# HWK_2_Schematic.net
KiCad netlist of a schematic drawn in EAGLE
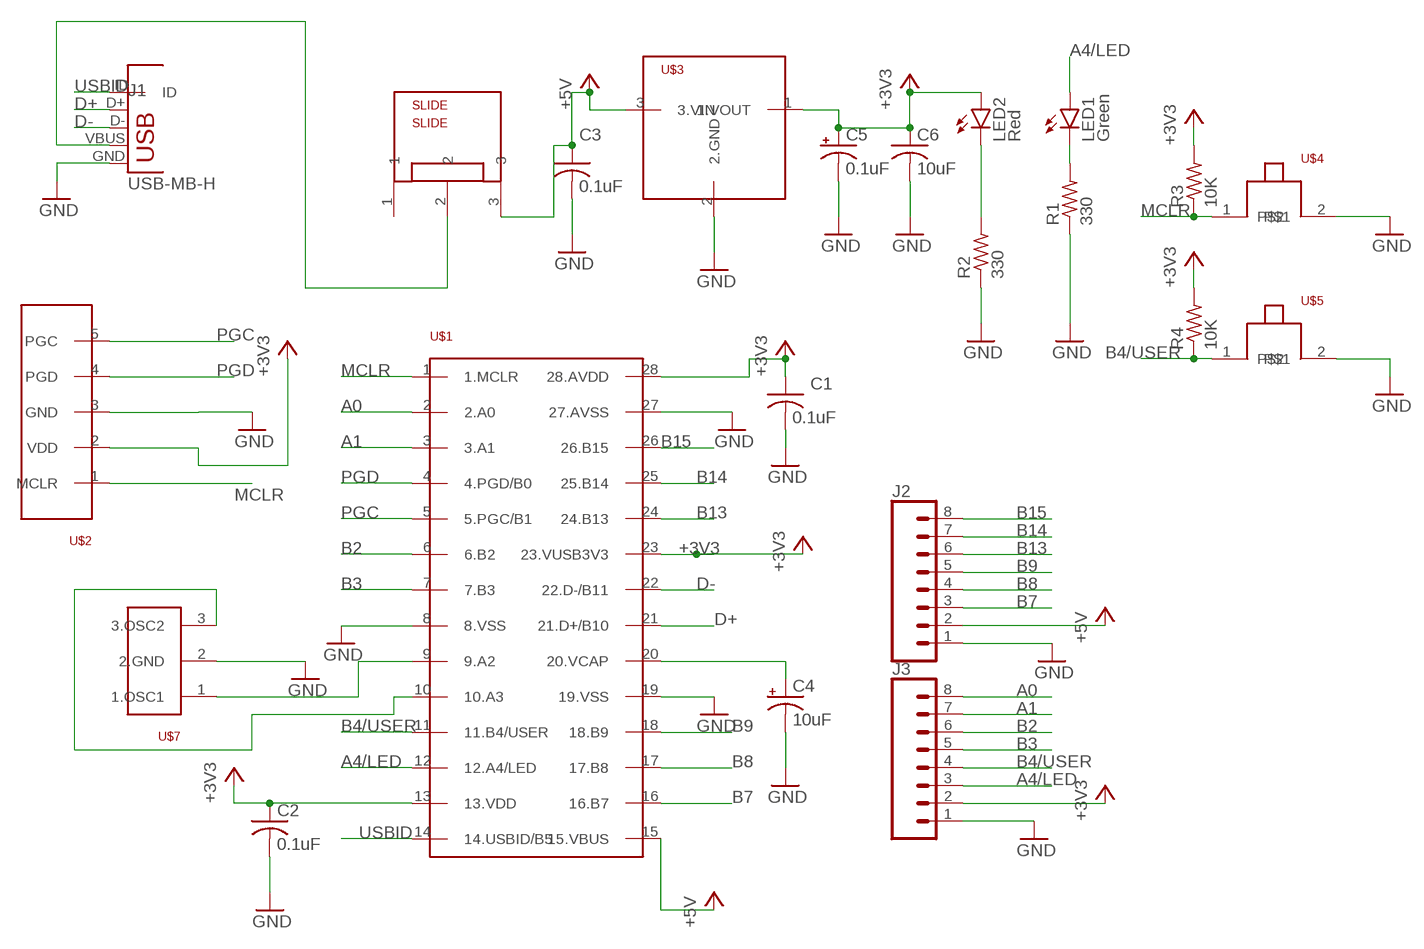
[diagram p0: schematic, sheet 1]

(export (version "E")
  (design (tool "Eeschema 10.0.6"))
  (components
    (comp (ref "C1")
      (value "0.1uF")
      (footprint "eagle-import:C025-025X050")
      (libsource (lib "eagle-import") (part "C-US025-025X050"))
    )
    (comp (ref "C2")
      (value "0.1uF")
      (footprint "eagle-import:C025-025X050")
      (libsource (lib "eagle-import") (part "C-US025-025X050"))
    )
    (comp (ref "C3")
      (value "0.1uF")
      (footprint "eagle-import:C025-025X050")
      (libsource (lib "eagle-import") (part "C-US025-025X050"))
    )
    (comp (ref "C4")
      (value "10uF")
      (footprint "eagle-import:B45181B")
      (libsource (lib "eagle-import") (part "CPOL-USB45181B"))
    )
    (comp (ref "C5")
      (value "0.1uF")
      (footprint "eagle-import:B45181B")
      (libsource (lib "eagle-import") (part "CPOL-USB45181B"))
    )
    (comp (ref "C6")
      (value "10uF")
      (footprint "eagle-import:C025-025X050")
      (libsource (lib "eagle-import") (part "C-US025-025X050"))
    )
    (comp (ref "J1")
      (value "USB-MB-H")
      (footprint "eagle-import:USB-MB-H")
      (libsource (lib "eagle-import") (part "USB-MB-H"))
    )
    (comp (ref "J2")
      (value "CONN_08NO_SILK_FEMALE_PTH")
      (footprint "eagle-import:1X08_NO_SILK")
      (libsource (lib "eagle-import") (part "CONN_08NO_SILK_FEMALE_PTH"))
    )
    (comp (ref "J3")
      (value "CONN_08NO_SILK_FEMALE_PTH")
      (footprint "eagle-import:1X08_NO_SILK")
      (libsource (lib "eagle-import") (part "CONN_08NO_SILK_FEMALE_PTH"))
    )
    (comp (ref "LED1")
      (value "Green")
      (footprint "eagle-import:LED3MM")
      (libsource (lib "eagle-import") (part "LED3MM"))
    )
    (comp (ref "LED2")
      (value "Red")
      (footprint "eagle-import:LED3MM")
      (libsource (lib "eagle-import") (part "LED3MM"))
    )
    (comp (ref "R1")
      (value "330")
      (footprint "eagle-import:0207_10")
      (libsource (lib "eagle-import") (part "R-US_0207/10"))
    )
    (comp (ref "R2")
      (value "330")
      (footprint "eagle-import:0207_10")
      (libsource (lib "eagle-import") (part "R-US_0207/10"))
    )
    (comp (ref "R3")
      (value "10K")
      (footprint "eagle-import:0207_10")
      (libsource (lib "eagle-import") (part "R-US_0207/10"))
    )
    (comp (ref "R4")
      (value "10K")
      (footprint "eagle-import:0207_10")
      (libsource (lib "eagle-import") (part "R-US_0207/10"))
    )
    (comp (ref "SLIDE")
      (value "SLIDE")
      (footprint "eagle-import:SLIDE")
      (libsource (lib "eagle-import") (part "SLIDE"))
    )
    (comp (ref "U$1")
      (value "PIC32MX250F128B")
      (footprint "eagle-import:DIL28-3")
      (libsource (lib "eagle-import") (part "PIC32MX250F128B"))
    )
    (comp (ref "U$2")
      (value "PICKIT3")
      (footprint "eagle-import:PICKIT3")
      (libsource (lib "eagle-import") (part "PICKIT3"))
    )
    (comp (ref "U$3")
      (value "VOLTAGE_REGULATOR")
      (footprint "eagle-import:TO92")
      (libsource (lib "eagle-import") (part "VOLTAGE_REGULATOR"))
    )
    (comp (ref "U$4")
      (value "PUSH_BUTTON")
      (footprint "eagle-import:PUSH_BUTTON")
      (libsource (lib "eagle-import") (part "PUSH_BUTTON"))
    )
    (comp (ref "U$5")
      (value "USER_BUTTON")
      (footprint "eagle-import:PUSH_BUTTON")
      (libsource (lib "eagle-import") (part "PUSH_BUTTON"))
    )
    (comp (ref "U$7")
      (value "8MHz")
      (footprint "eagle-import:OSC")
      (libsource (lib "eagle-import") (part "OSC"))
    )
  )
  (nets
    (net (code "1") (name "+3V3") (class "Default")
      (node (ref "C1") (pin "1") (pinfunction "1_1") (pintype "passive"))
      (node (ref "C2") (pin "1") (pinfunction "1_1") (pintype "passive"))
      (node (ref "C5") (pin "+") (pinfunction "+_+") (pintype "passive"))
      (node (ref "C6") (pin "1") (pinfunction "1_1") (pintype "passive"))
      (node (ref "J3") (pin "2") (pinfunction "2_2") (pintype "passive"))
      (node (ref "LED2") (pin "A") (pinfunction "A_A") (pintype "passive"))
      (node (ref "R3") (pin "2") (pinfunction "2_2") (pintype "passive"))
      (node (ref "R4") (pin "2") (pinfunction "2_2") (pintype "passive"))
      (node (ref "U$1") (pin "13") (pinfunction "13.VDD_13") (pintype "bidirectional"))
      (node (ref "U$1") (pin "23") (pinfunction "23.VUSB3V3_23") (pintype "bidirectional"))
      (node (ref "U$1") (pin "28") (pinfunction "28.AVDD_28") (pintype "bidirectional"))
      (node (ref "U$2") (pin "2") (pinfunction "VDD_2") (pintype "bidirectional"))
      (node (ref "U$3") (pin "1") (pinfunction "1.VOUT_1") (pintype "bidirectional"))
    )
    (net (code "2") (name "+5V") (class "Default")
      (node (ref "C3") (pin "1") (pinfunction "1_1") (pintype "passive"))
      (node (ref "J2") (pin "2") (pinfunction "2_2") (pintype "passive"))
      (node (ref "SLIDE") (pin "3") (pinfunction "3_3") (pintype "bidirectional"))
      (node (ref "U$1") (pin "15") (pinfunction "15.VBUS_15") (pintype "bidirectional"))
      (node (ref "U$3") (pin "3") (pinfunction "3.VIN_3") (pintype "bidirectional"))
    )
    (net (code "3") (name "/A0") (class "Default")
      (node (ref "J3") (pin "8") (pinfunction "8_8") (pintype "passive"))
      (node (ref "U$1") (pin "2") (pinfunction "2.A0_2") (pintype "bidirectional"))
    )
    (net (code "4") (name "/A1") (class "Default")
      (node (ref "J3") (pin "7") (pinfunction "7_7") (pintype "passive"))
      (node (ref "U$1") (pin "3") (pinfunction "3.A1_3") (pintype "bidirectional"))
    )
    (net (code "5") (name "/A4{slash}LED") (class "Default")
      (node (ref "J3") (pin "3") (pinfunction "3_3") (pintype "passive"))
      (node (ref "LED1") (pin "A") (pinfunction "A_A") (pintype "passive"))
      (node (ref "U$1") (pin "12") (pinfunction "12.A4/LED_12") (pintype "bidirectional"))
    )
    (net (code "6") (name "/B2") (class "Default")
      (node (ref "J3") (pin "6") (pinfunction "6_6") (pintype "passive"))
      (node (ref "U$1") (pin "6") (pinfunction "6.B2_6") (pintype "bidirectional"))
    )
    (net (code "7") (name "/B3") (class "Default")
      (node (ref "J3") (pin "5") (pinfunction "5_5") (pintype "passive"))
      (node (ref "U$1") (pin "7") (pinfunction "7.B3_7") (pintype "bidirectional"))
    )
    (net (code "8") (name "/B4{slash}USER") (class "Default")
      (node (ref "J3") (pin "4") (pinfunction "4_4") (pintype "passive"))
      (node (ref "R4") (pin "1") (pinfunction "1_1") (pintype "passive"))
      (node (ref "U$1") (pin "11") (pinfunction "11.B4/USER_11") (pintype "bidirectional"))
      (node (ref "U$5") (pin "1") (pinfunction "P$1_1") (pintype "bidirectional"))
    )
    (net (code "9") (name "/B7") (class "Default")
      (node (ref "J2") (pin "3") (pinfunction "3_3") (pintype "passive"))
      (node (ref "U$1") (pin "16") (pinfunction "16.B7_16") (pintype "bidirectional"))
    )
    (net (code "10") (name "/B8") (class "Default")
      (node (ref "J2") (pin "4") (pinfunction "4_4") (pintype "passive"))
      (node (ref "U$1") (pin "17") (pinfunction "17.B8_17") (pintype "bidirectional"))
    )
    (net (code "11") (name "/B9") (class "Default")
      (node (ref "J2") (pin "5") (pinfunction "5_5") (pintype "passive"))
      (node (ref "U$1") (pin "18") (pinfunction "18.B9_18") (pintype "bidirectional"))
    )
    (net (code "12") (name "/B13") (class "Default")
      (node (ref "J2") (pin "6") (pinfunction "6_6") (pintype "passive"))
      (node (ref "U$1") (pin "24") (pinfunction "24.B13_24") (pintype "bidirectional"))
    )
    (net (code "13") (name "/B14") (class "Default")
      (node (ref "J2") (pin "7") (pinfunction "7_7") (pintype "passive"))
      (node (ref "U$1") (pin "25") (pinfunction "25.B14_25") (pintype "bidirectional"))
    )
    (net (code "14") (name "/B15") (class "Default")
      (node (ref "J2") (pin "8") (pinfunction "8_8") (pintype "passive"))
      (node (ref "U$1") (pin "26") (pinfunction "26.B15_26") (pintype "bidirectional"))
    )
    (net (code "15") (name "/D+") (class "Default")
      (node (ref "J1") (pin "D+") (pinfunction "D+_D+") (pintype "bidirectional"))
      (node (ref "U$1") (pin "21") (pinfunction "21.D+/B10_21") (pintype "bidirectional"))
    )
    (net (code "16") (name "/D-") (class "Default")
      (node (ref "J1") (pin "D-") (pinfunction "D-_D-") (pintype "bidirectional"))
      (node (ref "U$1") (pin "22") (pinfunction "22.D-/B11_22") (pintype "bidirectional"))
    )
    (net (code "17") (name "/MCLR") (class "Default")
      (node (ref "R3") (pin "1") (pinfunction "1_1") (pintype "passive"))
      (node (ref "U$1") (pin "1") (pinfunction "1.MCLR_1") (pintype "bidirectional"))
      (node (ref "U$2") (pin "1") (pinfunction "MCLR_1") (pintype "bidirectional"))
      (node (ref "U$4") (pin "1") (pinfunction "P$1_1") (pintype "bidirectional"))
    )
    (net (code "18") (name "/PGC") (class "Default")
      (node (ref "U$1") (pin "5") (pinfunction "5.PGC/B1_5") (pintype "bidirectional"))
      (node (ref "U$2") (pin "5") (pinfunction "PGC_5") (pintype "bidirectional"))
    )
    (net (code "19") (name "/PGD") (class "Default")
      (node (ref "U$1") (pin "4") (pinfunction "4.PGD/B0_4") (pintype "bidirectional"))
      (node (ref "U$2") (pin "4") (pinfunction "PGD_4") (pintype "bidirectional"))
    )
    (net (code "20") (name "/USBID") (class "Default")
      (node (ref "J1") (pin "ID") (pinfunction "ID_ID") (pintype "bidirectional"))
      (node (ref "U$1") (pin "14") (pinfunction "14.USBID/B5_14") (pintype "bidirectional"))
    )
    (net (code "21") (name "GND") (class "Default")
      (node (ref "C1") (pin "2") (pinfunction "2_2") (pintype "passive"))
      (node (ref "C2") (pin "2") (pinfunction "2_2") (pintype "passive"))
      (node (ref "C3") (pin "2") (pinfunction "2_2") (pintype "passive"))
      (node (ref "C4") (pin "-") (pinfunction "-_-") (pintype "passive"))
      (node (ref "C5") (pin "-") (pinfunction "-_-") (pintype "passive"))
      (node (ref "C6") (pin "2") (pinfunction "2_2") (pintype "passive"))
      (node (ref "J1") (pin "GND") (pinfunction "GND_GND") (pintype "bidirectional"))
      (node (ref "J2") (pin "1") (pinfunction "1_1") (pintype "passive"))
      (node (ref "J3") (pin "1") (pinfunction "1_1") (pintype "passive"))
      (node (ref "R1") (pin "1") (pinfunction "1_1") (pintype "passive"))
      (node (ref "R2") (pin "1") (pinfunction "1_1") (pintype "passive"))
      (node (ref "U$1") (pin "19") (pinfunction "19.VSS_19") (pintype "bidirectional"))
      (node (ref "U$1") (pin "27") (pinfunction "27.AVSS_27") (pintype "bidirectional"))
      (node (ref "U$1") (pin "8") (pinfunction "8.VSS_8") (pintype "bidirectional"))
      (node (ref "U$2") (pin "3") (pinfunction "GND_3") (pintype "bidirectional"))
      (node (ref "U$3") (pin "2") (pinfunction "2.GND_2") (pintype "bidirectional"))
      (node (ref "U$4") (pin "2") (pinfunction "P$2_2") (pintype "bidirectional"))
      (node (ref "U$5") (pin "2") (pinfunction "P$2_2") (pintype "bidirectional"))
      (node (ref "U$7") (pin "2") (pinfunction "2.GND_2") (pintype "bidirectional"))
    )
    (net (code "22") (name "Net-(J1-PadVBUS)") (class "Default")
      (node (ref "J1") (pin "VBUS") (pinfunction "VBUS_VBUS") (pintype "bidirectional"))
      (node (ref "SLIDE") (pin "2") (pinfunction "2_2") (pintype "bidirectional"))
    )
    (net (code "23") (name "Net-(LED1-C)") (class "Default")
      (node (ref "LED1") (pin "K") (pinfunction "C_K") (pintype "passive"))
      (node (ref "R1") (pin "2") (pinfunction "2_2") (pintype "passive"))
    )
    (net (code "24") (name "Net-(LED2-C)") (class "Default")
      (node (ref "LED2") (pin "K") (pinfunction "C_K") (pintype "passive"))
      (node (ref "R2") (pin "2") (pinfunction "2_2") (pintype "passive"))
    )
    (net (code "25") (name "Net-(U$1-9.A2)") (class "Default")
      (node (ref "U$1") (pin "9") (pinfunction "9.A2_9") (pintype "bidirectional"))
      (node (ref "U$7") (pin "1") (pinfunction "1.OSC1_1") (pintype "bidirectional"))
    )
    (net (code "26") (name "Net-(U$1-10.A3)") (class "Default")
      (node (ref "U$1") (pin "10") (pinfunction "10.A3_10") (pintype "bidirectional"))
      (node (ref "U$7") (pin "3") (pinfunction "3.OSC2_3") (pintype "bidirectional"))
    )
    (net (code "27") (name "Net-(U$1-20.VCAP)") (class "Default")
      (node (ref "C4") (pin "+") (pinfunction "+_+") (pintype "passive"))
      (node (ref "U$1") (pin "20") (pinfunction "20.VCAP_20") (pintype "bidirectional"))
    )
    (net (code "28") (name "unconnected-(SLIDE-Pad1)") (class "Default")
      (node (ref "SLIDE") (pin "1") (pinfunction "1_1") (pintype "bidirectional"))
    )
  )
)
